# Rs485_current_sense_V1_1.net
KiCad netlist of a schematic drawn in EAGLE
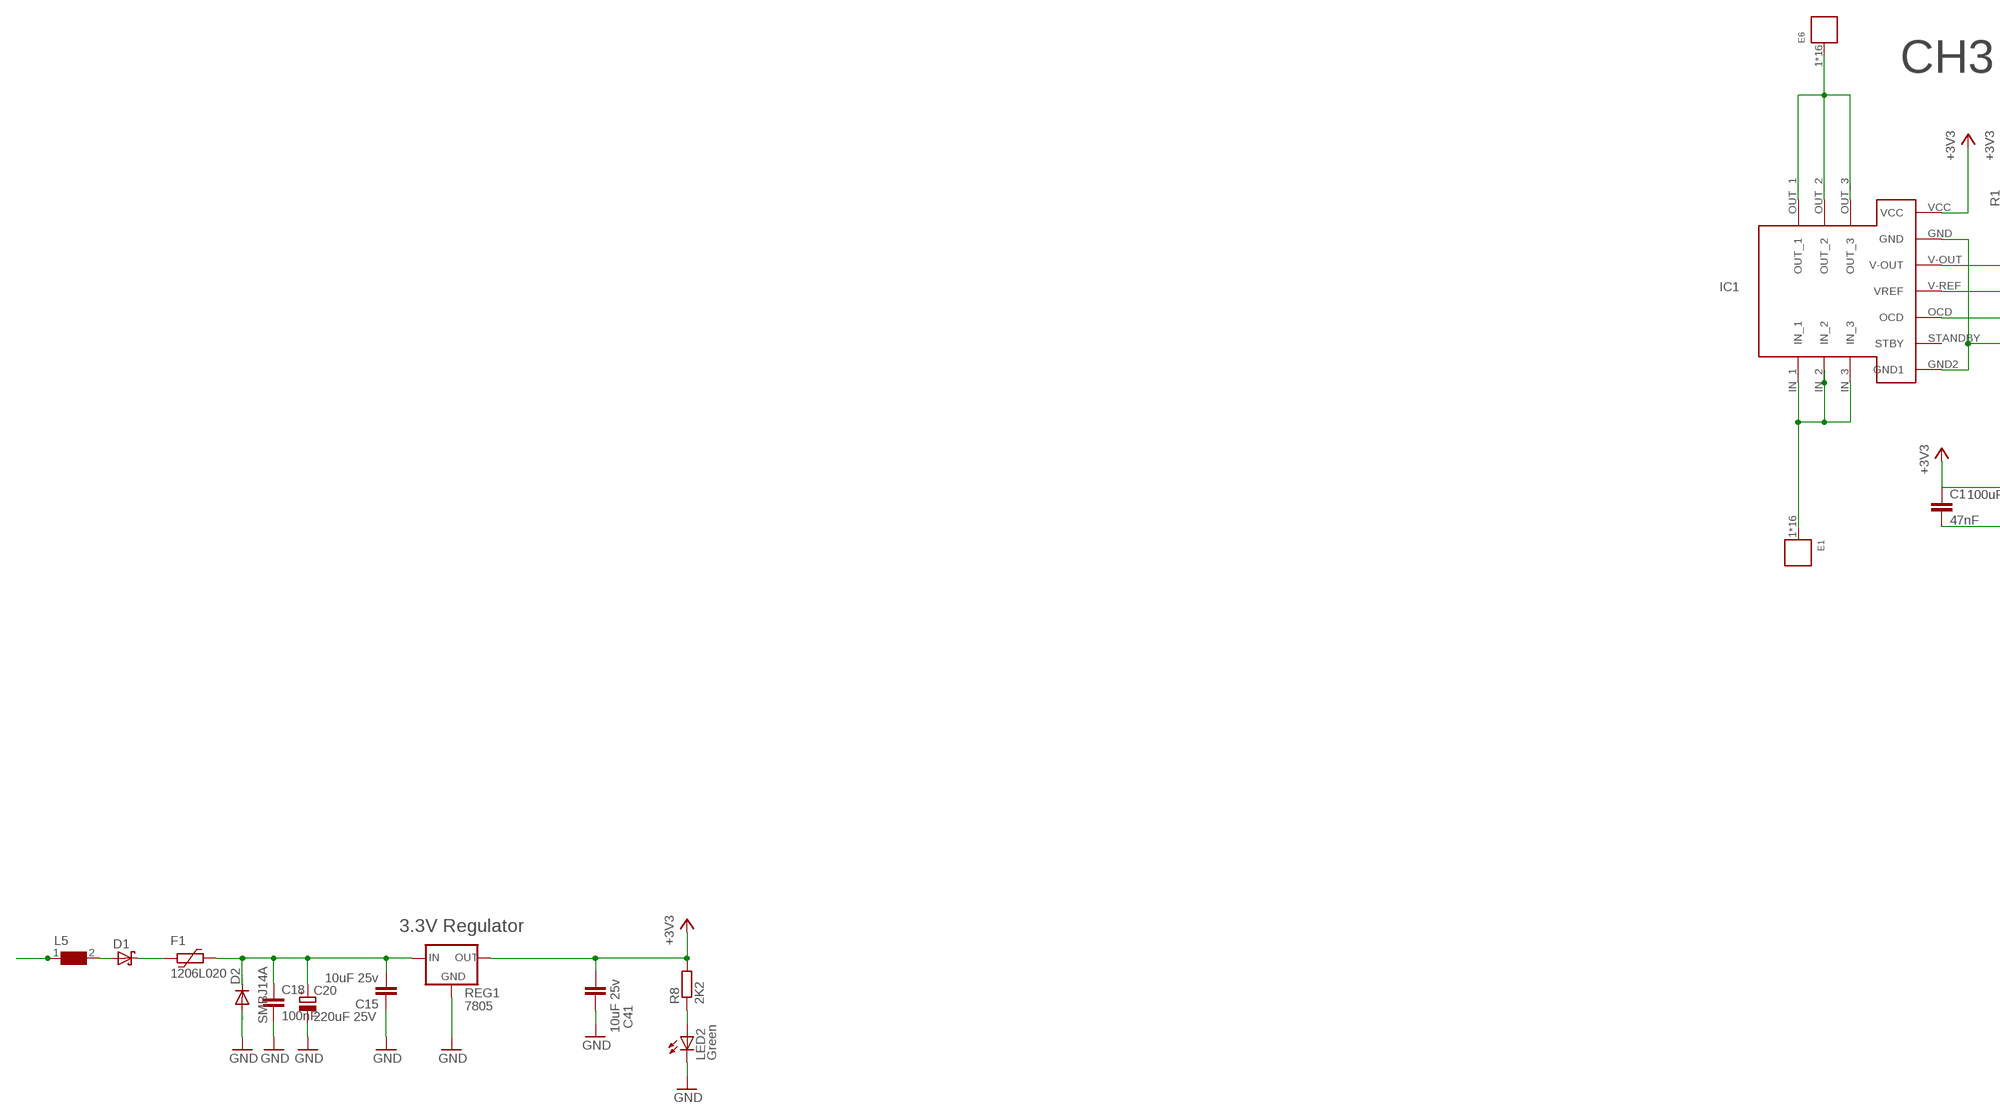
[diagram p0: schematic, sheet 1, part 1 of 3]
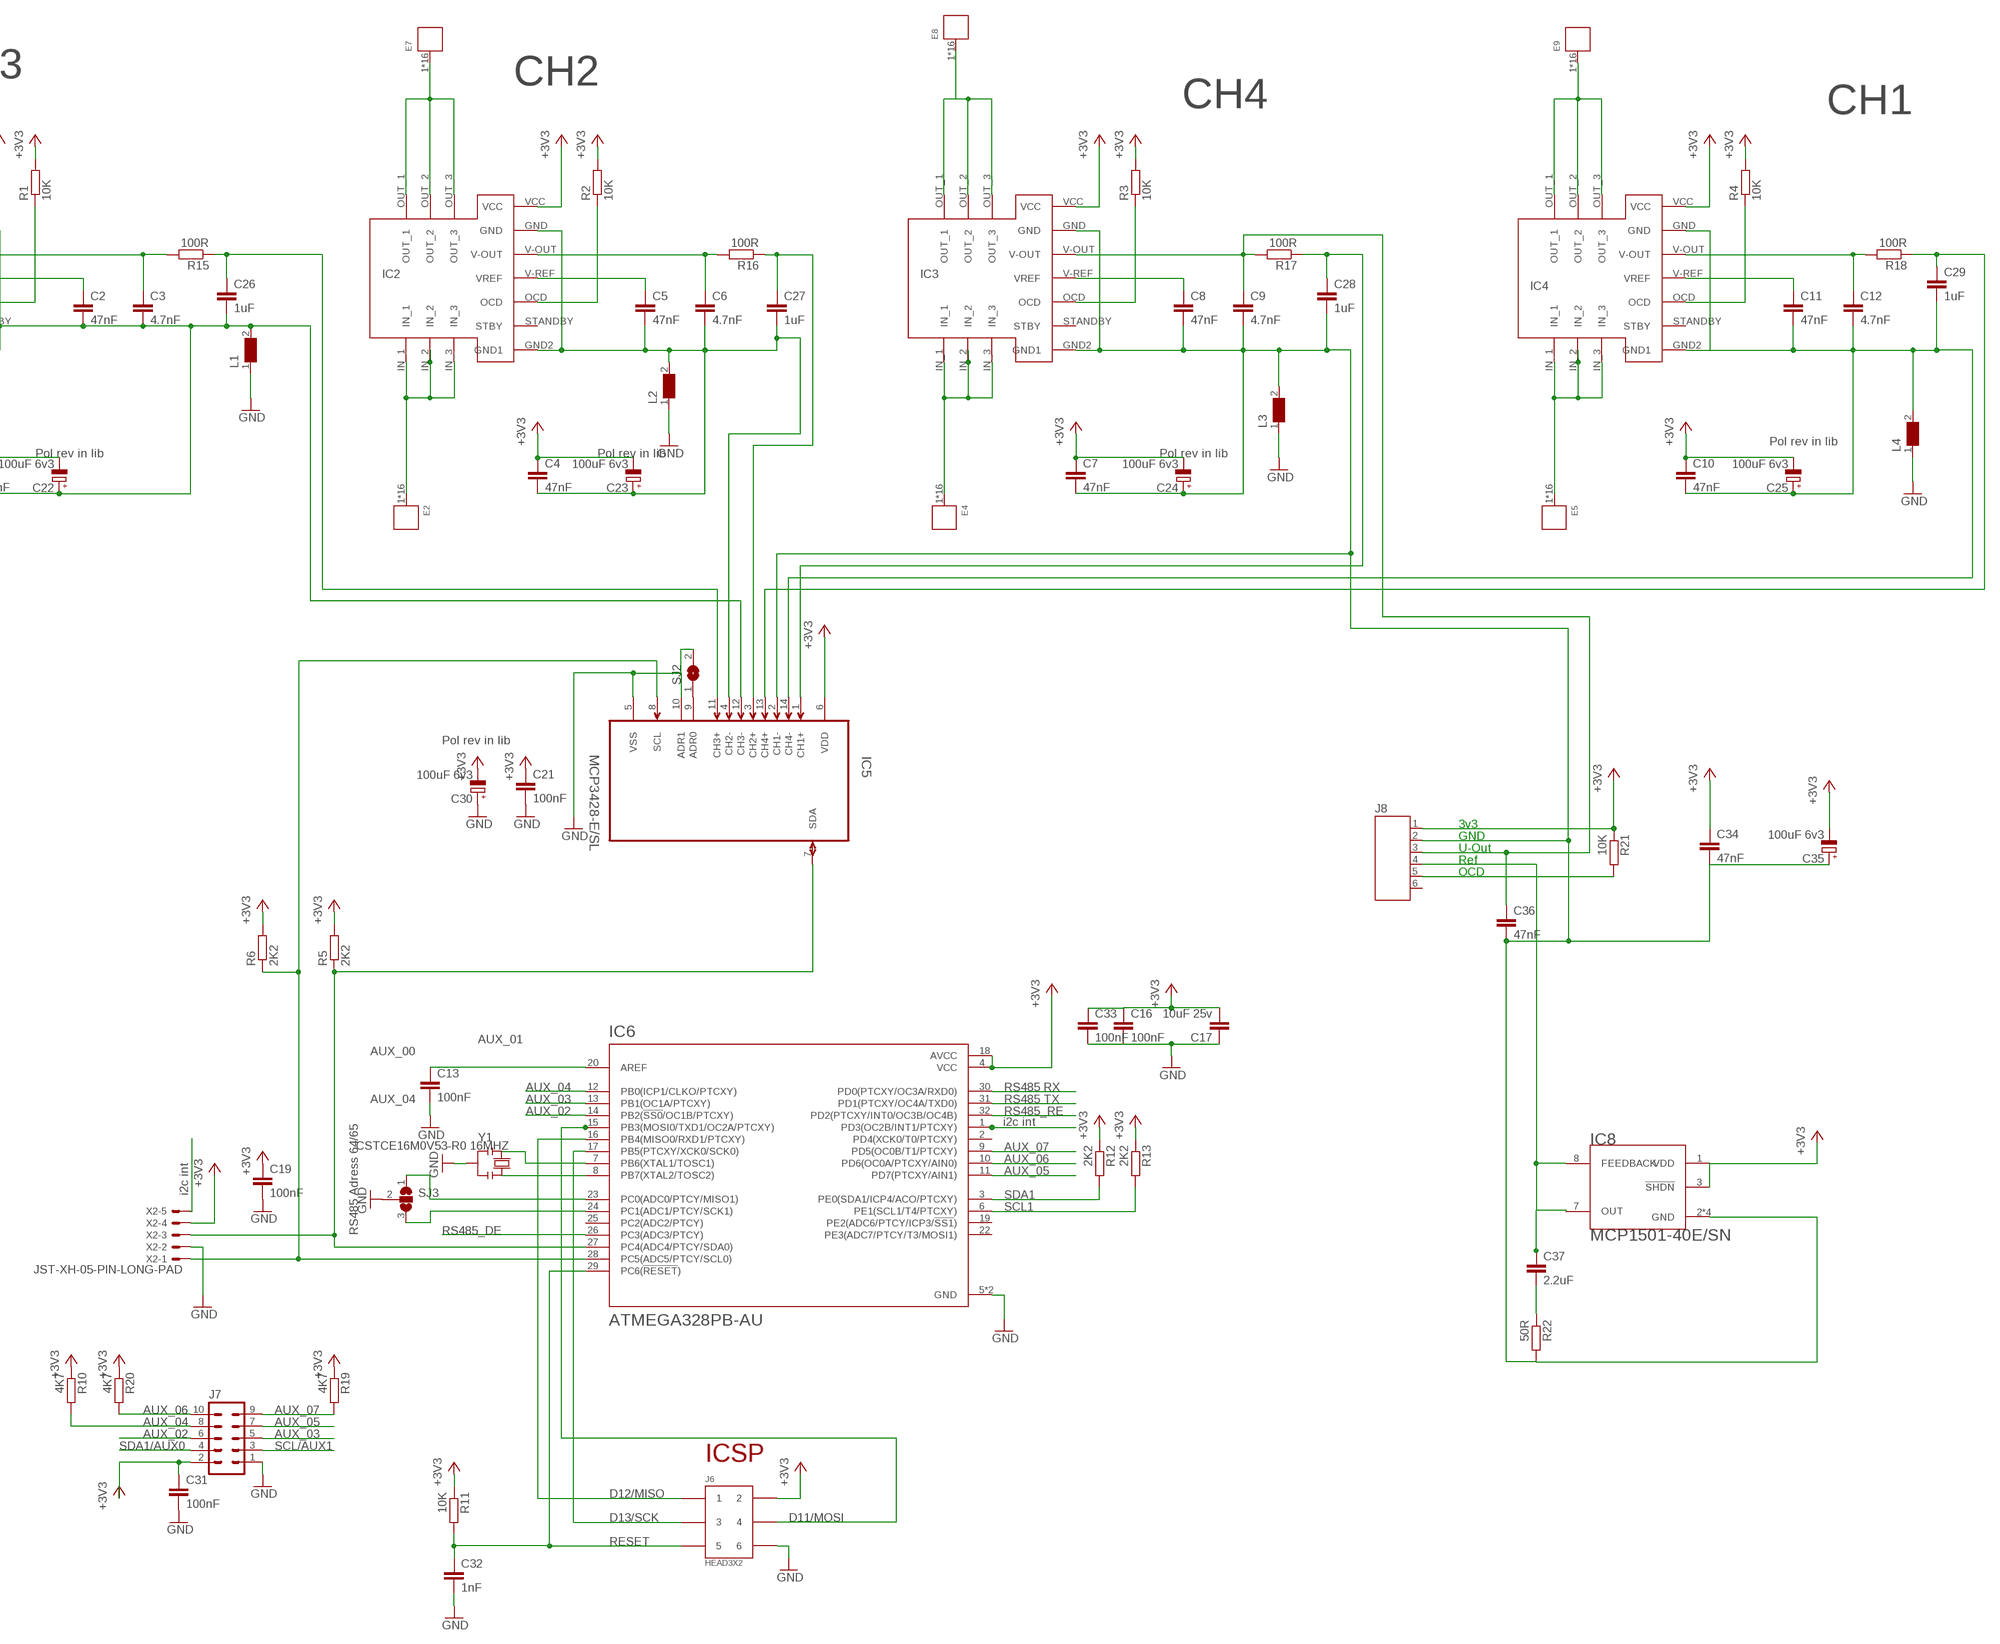
[diagram p1: schematic, sheet 1, part 2 of 3]
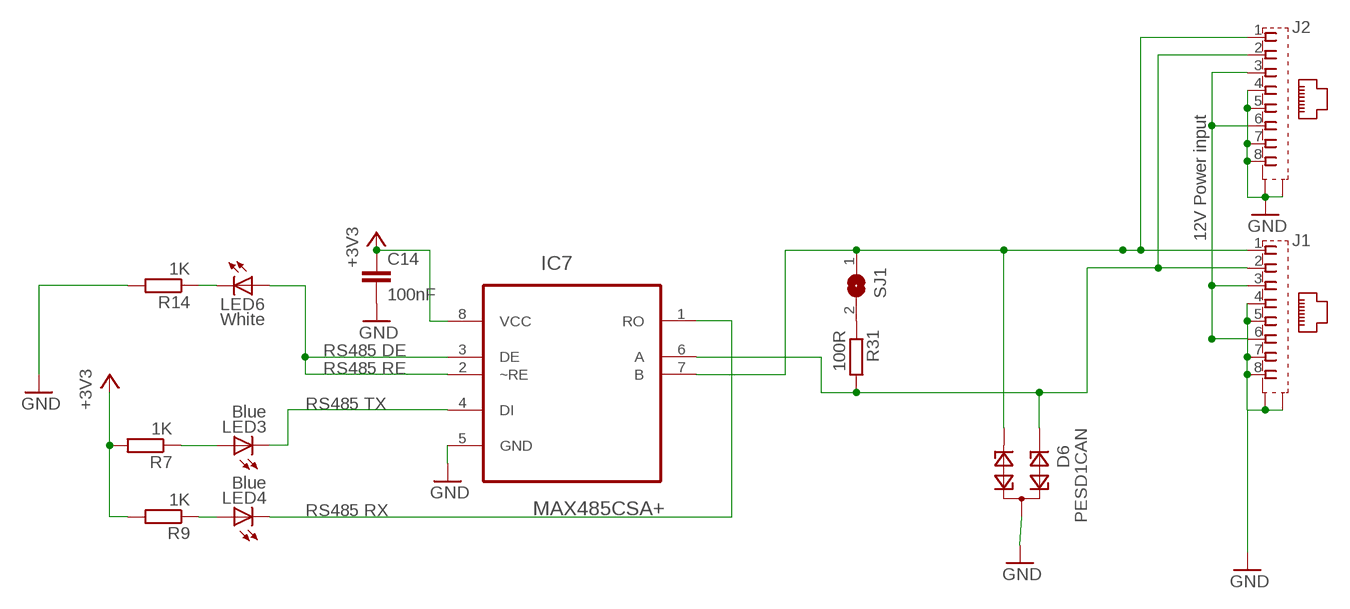
[diagram p2: schematic, sheet 1, part 3 of 3]

(export (version "E")
  (design (tool "Eeschema 10.0.6"))
  (components
    (comp (ref "C1")
      (value "47nF")
      (footprint "eagle-import:C0603")
      (libsource (lib "eagle-import") (part "C-EUC0603"))
    )
    (comp (ref "C2")
      (value "47nF")
      (footprint "eagle-import:C0603")
      (libsource (lib "eagle-import") (part "C-EUC0603"))
    )
    (comp (ref "C3")
      (value "4.7nF")
      (footprint "eagle-import:C0603")
      (libsource (lib "eagle-import") (part "C-EUC0603"))
    )
    (comp (ref "C4")
      (value "47nF")
      (footprint "eagle-import:C0603")
      (libsource (lib "eagle-import") (part "C-EUC0603"))
    )
    (comp (ref "C5")
      (value "47nF")
      (footprint "eagle-import:C0603")
      (libsource (lib "eagle-import") (part "C-EUC0603"))
    )
    (comp (ref "C6")
      (value "4.7nF")
      (footprint "eagle-import:C0603")
      (libsource (lib "eagle-import") (part "C-EUC0603"))
    )
    (comp (ref "C7")
      (value "47nF")
      (footprint "eagle-import:C0603")
      (libsource (lib "eagle-import") (part "C-EUC0603"))
    )
    (comp (ref "C8")
      (value "47nF")
      (footprint "eagle-import:C0603")
      (libsource (lib "eagle-import") (part "C-EUC0603"))
    )
    (comp (ref "C9")
      (value "4.7nF")
      (footprint "eagle-import:C0603")
      (libsource (lib "eagle-import") (part "C-EUC0603"))
    )
    (comp (ref "C10")
      (value "47nF")
      (footprint "eagle-import:C0603")
      (libsource (lib "eagle-import") (part "C-EUC0603"))
    )
    (comp (ref "C11")
      (value "47nF")
      (footprint "eagle-import:C0603")
      (libsource (lib "eagle-import") (part "C-EUC0603"))
    )
    (comp (ref "C12")
      (value "4.7nF")
      (footprint "eagle-import:C0603")
      (libsource (lib "eagle-import") (part "C-EUC0603"))
    )
    (comp (ref "C13")
      (value "100nF")
      (footprint "eagle-import:C0603")
      (libsource (lib "eagle-import") (part "C-EUC0603"))
    )
    (comp (ref "C14")
      (value "100nF")
      (footprint "eagle-import:C0603")
      (libsource (lib "eagle-import") (part "resistor_C-EUC0603"))
    )
    (comp (ref "C15")
      (value "10uF 25v")
      (footprint "eagle-import:C1206")
      (libsource (lib "eagle-import") (part "resistor_C-EUC1206"))
    )
    (comp (ref "C16")
      (value "100nF")
      (footprint "eagle-import:C0603")
      (libsource (lib "eagle-import") (part "C-EUC0603"))
    )
    (comp (ref "C17")
      (value "10uF 25v")
      (footprint "eagle-import:C1206")
      (libsource (lib "eagle-import") (part "resistor_C-EUC1206"))
    )
    (comp (ref "C18")
      (value "100nF")
      (footprint "eagle-import:C0603")
      (libsource (lib "eagle-import") (part "C-EUC0603"))
    )
    (comp (ref "C19")
      (value "100nF")
      (footprint "eagle-import:C0603")
      (libsource (lib "eagle-import") (part "C-EUC0603"))
    )
    (comp (ref "C20")
      (value "220uF 25V")
      (footprint "eagle-import:PANASONIC_F")
      (libsource (lib "eagle-import") (part "CPOL-EUF"))
    )
    (comp (ref "C21")
      (value "100nF")
      (footprint "eagle-import:C0603")
      (libsource (lib "eagle-import") (part "C-EUC0603"))
    )
    (comp (ref "C22")
      (value "100uF 6v3")
      (footprint "eagle-import:CT3528")
      (libsource (lib "eagle-import") (part "resistor_CPOL-EUCT3528"))
    )
    (comp (ref "C23")
      (value "100uF 6v3")
      (footprint "eagle-import:CT3528")
      (libsource (lib "eagle-import") (part "resistor_CPOL-EUCT3528"))
    )
    (comp (ref "C24")
      (value "100uF 6v3")
      (footprint "eagle-import:CT3528")
      (libsource (lib "eagle-import") (part "resistor_CPOL-EUCT3528"))
    )
    (comp (ref "C25")
      (value "100uF 6v3")
      (footprint "eagle-import:CT3528")
      (libsource (lib "eagle-import") (part "resistor_CPOL-EUCT3528"))
    )
    (comp (ref "C26")
      (value "1uF")
      (footprint "eagle-import:C0603")
      (libsource (lib "eagle-import") (part "C-EUC0603"))
    )
    (comp (ref "C27")
      (value "1uF")
      (footprint "eagle-import:C0603")
      (libsource (lib "eagle-import") (part "C-EUC0603"))
    )
    (comp (ref "C28")
      (value "1uF")
      (footprint "eagle-import:C0603")
      (libsource (lib "eagle-import") (part "C-EUC0603"))
    )
    (comp (ref "C29")
      (value "1uF")
      (footprint "eagle-import:C0603")
      (libsource (lib "eagle-import") (part "C-EUC0603"))
    )
    (comp (ref "C30")
      (value "100uF 6v3")
      (footprint "eagle-import:CT3528")
      (libsource (lib "eagle-import") (part "resistor_CPOL-EUCT3528"))
    )
    (comp (ref "C31")
      (value "100nF")
      (footprint "eagle-import:C0603")
      (libsource (lib "eagle-import") (part "C-EUC0603"))
    )
    (comp (ref "C32")
      (value "1nF")
      (footprint "eagle-import:C0603")
      (libsource (lib "eagle-import") (part "C-EUC0603"))
    )
    (comp (ref "C33")
      (value "100nF")
      (footprint "eagle-import:C0603")
      (libsource (lib "eagle-import") (part "C-EUC0603"))
    )
    (comp (ref "C34")
      (value "47nF")
      (footprint "eagle-import:C0603")
      (libsource (lib "eagle-import") (part "C-EUC0603"))
    )
    (comp (ref "C35")
      (value "100uF 6v3")
      (footprint "eagle-import:CT3528")
      (libsource (lib "eagle-import") (part "resistor_CPOL-EUCT3528"))
    )
    (comp (ref "C36")
      (value "47nF")
      (footprint "eagle-import:C0603")
      (libsource (lib "eagle-import") (part "C-EUC0603"))
    )
    (comp (ref "C37")
      (value "2.2uF")
      (footprint "eagle-import:C0805")
      (libsource (lib "eagle-import") (part "resistor_C-EUC0805"))
    )
    (comp (ref "C41")
      (value "10uF 25v")
      (footprint "eagle-import:C1206")
      (libsource (lib "eagle-import") (part "resistor_C-EUC1206"))
    )
    (comp (ref "D1")
      (value "SCHOTTKY-DIODESMD")
      (footprint "eagle-import:SMB")
      (libsource (lib "eagle-import") (part "SCHOTTKY-DIODESMD"))
    )
    (comp (ref "D2")
      (value "SMBJ14A")
      (footprint "eagle-import:DO214AC")
      (libsource (lib "eagle-import") (part "DIODE-DO214AC"))
    )
    (comp (ref "D6")
      (value "PESD1CAN")
      (footprint "eagle-import:SOT23")
      (libsource (lib "eagle-import") (part "PESD1CAN"))
    )
    (comp (ref "E1")
      (value "WP-BUFU_J(10)")
      (footprint "eagle-import:16PINS_10X10_FULL")
      (libsource (lib "eagle-import") (part "WP-BUFU_J(10)"))
    )
    (comp (ref "E2")
      (value "WP-BUFU_J(10)")
      (footprint "eagle-import:16PINS_10X10_FULL")
      (libsource (lib "eagle-import") (part "WP-BUFU_J(10)"))
    )
    (comp (ref "E4")
      (value "WP-BUFU_J(10)")
      (footprint "eagle-import:16PINS_10X10_FULL")
      (libsource (lib "eagle-import") (part "WP-BUFU_J(10)"))
    )
    (comp (ref "E5")
      (value "WP-BUFU_J(10)")
      (footprint "eagle-import:16PINS_10X10_FULL")
      (libsource (lib "eagle-import") (part "WP-BUFU_J(10)"))
    )
    (comp (ref "E6")
      (value "WP-BUFU_J(10)")
      (footprint "eagle-import:16PINS_10X10_FULL")
      (libsource (lib "eagle-import") (part "WP-BUFU_J(10)"))
    )
    (comp (ref "E7")
      (value "WP-BUFU_J(10)")
      (footprint "eagle-import:16PINS_10X10_FULL")
      (libsource (lib "eagle-import") (part "WP-BUFU_J(10)"))
    )
    (comp (ref "E8")
      (value "WP-BUFU_J(10)")
      (footprint "eagle-import:16PINS_10X10_FULL")
      (libsource (lib "eagle-import") (part "WP-BUFU_J(10)"))
    )
    (comp (ref "E9")
      (value "WP-BUFU_J(10)")
      (footprint "eagle-import:16PINS_10X10_FULL")
      (libsource (lib "eagle-import") (part "WP-BUFU_J(10)"))
    )
    (comp (ref "F1")
      (value "1206L020")
      (footprint "eagle-import:1206L")
      (fields (field (name "MF") "Littelfuse"))
      (libsource (lib "eagle-import") (part "?1206L020"))
    )
    (comp (ref "IC1")
      (value "HO15-NP/SP33-1000")
      (footprint "eagle-import:HO15-NP_SP33-1000")
      (libsource (lib "eagle-import") (part "HO15-NP/SP33-1000"))
    )
    (comp (ref "IC2")
      (value "HO15-NP/SP33-1000")
      (footprint "eagle-import:HO15-NP_SP33-1000")
      (libsource (lib "eagle-import") (part "HO15-NP/SP33-1000"))
    )
    (comp (ref "IC3")
      (value "HO15-NP/SP33-1000")
      (footprint "eagle-import:HO15-NP_SP33-1000")
      (libsource (lib "eagle-import") (part "HO15-NP/SP33-1000"))
    )
    (comp (ref "IC4")
      (value "HO15-NP/SP33-1000")
      (footprint "eagle-import:HO15-NP_SP33-1000")
      (libsource (lib "eagle-import") (part "HO15-NP/SP33-1000"))
    )
    (comp (ref "IC5")
      (value "MCP3428-E/SL")
      (footprint "eagle-import:SOIC127P600X175-14N")
      (libsource (lib "eagle-import") (part "MCP3428-E/SL"))
    )
    (comp (ref "IC6")
      (value "ATMEGA328PB-AU")
      (footprint "eagle-import:QFP80P900X900X120-32N")
      (fields (field (name "MF") "Microchip"))
      (libsource (lib "eagle-import") (part "ATMEGA328PB-AU"))
    )
    (comp (ref "IC7")
      (value "MAX485CSA+")
      (footprint "eagle-import:SOIC127P600X175-8N")
      (libsource (lib "eagle-import") (part "MAX485CSA+"))
    )
    (comp (ref "IC8")
      (value "MCP1501-40E/SN")
      (footprint "eagle-import:SOIC127P600X175-8N")
      (fields (field (name "MF") "Microchip"))
      (libsource (lib "eagle-import") (part "MCP1501-40E/SN"))
    )
    (comp (ref "J1")
      (value "555153-1")
      (footprint "eagle-import:555153-1")
      (libsource (lib "eagle-import") (part "555153-1"))
    )
    (comp (ref "J2")
      (value "555153-1")
      (footprint "eagle-import:555153-1")
      (libsource (lib "eagle-import") (part "555153-1"))
    )
    (comp (ref "J6")
      (value "HEAD3X2")
      (footprint "eagle-import:HEAD3X2")
      (libsource (lib "eagle-import") (part "HEAD3X2"))
    )
    (comp (ref "J7")
      (value "MA05-2")
      (footprint "eagle-import:MA05-2")
      (libsource (lib "eagle-import") (part "MA05-2"))
    )
    (comp (ref "J8")
      (value "JST-PH6")
      (footprint "eagle-import:JST-PH6")
      (libsource (lib "eagle-import") (part "JST-PH6"))
    )
    (comp (ref "L1")
      (value "WE-CBF-74279209_0805")
      (footprint "eagle-import:0805")
      (fields (field (name "MPN") "74279209"))
      (libsource (lib "eagle-import") (part "WE-CBF_0805-74279209"))
    )
    (comp (ref "L2")
      (value "WE-CBF-74279209_0805")
      (footprint "eagle-import:0805")
      (fields (field (name "MPN") "74279209"))
      (libsource (lib "eagle-import") (part "WE-CBF_0805-74279209"))
    )
    (comp (ref "L3")
      (value "WE-CBF-74279209_0805")
      (footprint "eagle-import:0805")
      (fields (field (name "MPN") "74279209"))
      (libsource (lib "eagle-import") (part "WE-CBF_0805-74279209"))
    )
    (comp (ref "L4")
      (value "WE-CBF-74279209_0805")
      (footprint "eagle-import:0805")
      (fields (field (name "MPN") "74279209"))
      (libsource (lib "eagle-import") (part "WE-CBF_0805-74279209"))
    )
    (comp (ref "L5")
      (value "WE-CBF-7427922_1206")
      (footprint "eagle-import:1206")
      (fields (field (name "MPN") "7427922"))
      (libsource (lib "eagle-import") (part "WE-CBF_1206-7427922"))
    )
    (comp (ref "LED2")
      (value "Green")
      (footprint "eagle-import:CHIPLED_0805")
      (libsource (lib "eagle-import") (part "LEDCHIPLED_0805"))
    )
    (comp (ref "LED3")
      (value "Blue")
      (footprint "eagle-import:CHIPLED_0805")
      (libsource (lib "eagle-import") (part "LEDCHIPLED_0805"))
    )
    (comp (ref "LED4")
      (value "Blue")
      (footprint "eagle-import:CHIPLED_0805")
      (libsource (lib "eagle-import") (part "LEDCHIPLED_0805"))
    )
    (comp (ref "LED6")
      (value "White")
      (footprint "eagle-import:CHIPLED_0805")
      (libsource (lib "eagle-import") (part "LEDCHIPLED_0805"))
    )
    (comp (ref "R1")
      (value "10K")
      (footprint "eagle-import:R0603")
      (libsource (lib "eagle-import") (part "R-EU_R0603"))
    )
    (comp (ref "R2")
      (value "10K")
      (footprint "eagle-import:R0603")
      (libsource (lib "eagle-import") (part "R-EU_R0603"))
    )
    (comp (ref "R3")
      (value "10K")
      (footprint "eagle-import:R0603")
      (libsource (lib "eagle-import") (part "R-EU_R0603"))
    )
    (comp (ref "R4")
      (value "10K")
      (footprint "eagle-import:R0603")
      (libsource (lib "eagle-import") (part "R-EU_R0603"))
    )
    (comp (ref "R5")
      (value "2K2")
      (footprint "eagle-import:R0603")
      (libsource (lib "eagle-import") (part "R-EU_R0603"))
    )
    (comp (ref "R6")
      (value "2K2")
      (footprint "eagle-import:R0603")
      (libsource (lib "eagle-import") (part "R-EU_R0603"))
    )
    (comp (ref "R7")
      (value "1K")
      (footprint "eagle-import:R0805")
      (libsource (lib "eagle-import") (part "resistor_R-EU_R0805"))
    )
    (comp (ref "R8")
      (value "2K2")
      (footprint "eagle-import:R0805")
      (libsource (lib "eagle-import") (part "resistor_R-EU_R0805"))
    )
    (comp (ref "R9")
      (value "1K")
      (footprint "eagle-import:R0805")
      (libsource (lib "eagle-import") (part "resistor_R-EU_R0805"))
    )
    (comp (ref "R10")
      (value "4K7")
      (footprint "eagle-import:R0603")
      (libsource (lib "eagle-import") (part "resistor_R-EU_R0603"))
    )
    (comp (ref "R11")
      (value "10K")
      (footprint "eagle-import:R0603")
      (libsource (lib "eagle-import") (part "resistor_R-EU_R0603"))
    )
    (comp (ref "R12")
      (value "2K2")
      (footprint "eagle-import:R0603")
      (libsource (lib "eagle-import") (part "resistor_R-EU_R0603"))
    )
    (comp (ref "R13")
      (value "2K2")
      (footprint "eagle-import:R0603")
      (libsource (lib "eagle-import") (part "resistor_R-EU_R0603"))
    )
    (comp (ref "R14")
      (value "1K")
      (footprint "eagle-import:R0805")
      (libsource (lib "eagle-import") (part "resistor_R-EU_R0805"))
    )
    (comp (ref "R15")
      (value "100R")
      (footprint "eagle-import:R0603")
      (libsource (lib "eagle-import") (part "R-EU_R0603"))
    )
    (comp (ref "R16")
      (value "100R")
      (footprint "eagle-import:R0603")
      (libsource (lib "eagle-import") (part "R-EU_R0603"))
    )
    (comp (ref "R17")
      (value "100R")
      (footprint "eagle-import:R0603")
      (libsource (lib "eagle-import") (part "R-EU_R0603"))
    )
    (comp (ref "R18")
      (value "100R")
      (footprint "eagle-import:R0603")
      (libsource (lib "eagle-import") (part "R-EU_R0603"))
    )
    (comp (ref "R19")
      (value "4K7")
      (footprint "eagle-import:R0603")
      (libsource (lib "eagle-import") (part "resistor_R-EU_R0603"))
    )
    (comp (ref "R20")
      (value "4K7")
      (footprint "eagle-import:R0603")
      (libsource (lib "eagle-import") (part "resistor_R-EU_R0603"))
    )
    (comp (ref "R21")
      (value "10K")
      (footprint "eagle-import:R0603")
      (libsource (lib "eagle-import") (part "resistor_R-EU_R0603"))
    )
    (comp (ref "R22")
      (value "50R")
      (footprint "eagle-import:R0603")
      (libsource (lib "eagle-import") (part "resistor_R-EU_R0603"))
    )
    (comp (ref "R31")
      (value "100R")
      (footprint "eagle-import:R0805")
      (libsource (lib "eagle-import") (part "resistor_R-EU_R0805"))
    )
    (comp (ref "REG1")
      (value "7805")
      (footprint "eagle-import:78XXS")
      (libsource (lib "eagle-import") (part "78XXS"))
    )
    (comp (ref "SJ1") (value "SJ") (footprint "eagle-import:SJ") (libsource (lib "eagle-import") (part "SJ")))
    (comp (ref "SJ2") (value "SJ") (footprint "eagle-import:SJ") (libsource (lib "eagle-import") (part "SJ")))
    (comp (ref "SJ3")
      (value "SJ2W")
      (footprint "eagle-import:SJ_2")
      (libsource (lib "eagle-import") (part "SJ2W"))
    )
    (comp (ref "X2")
      (value "JST-XH-05-PIN-LONG-PAD")
      (footprint "eagle-import:JST-XH-05-PACKAGE-LONG-PAD")
      (libsource (lib "eagle-import") (part "JST-XH-05-PIN-LONG-PAD"))
    )
    (comp (ref "Y1")
      (value "CSTCE16M0V53-R0 16MHZ")
      (footprint "eagle-import:RESONATOR")
      (libsource (lib "eagle-import") (part "RESONATORMU"))
    )
  )
  (nets
    (net (code "1") (name "+3V3") (class "Default")
      (node (ref "C1") (pin "1") (pinfunction "1_1") (pintype "passive"))
      (node (ref "C10") (pin "1") (pinfunction "1_1") (pintype "passive"))
      (node (ref "C14") (pin "1") (pinfunction "1_1") (pintype "passive"))
      (node (ref "C16") (pin "1") (pinfunction "1_1") (pintype "passive"))
      (node (ref "C17") (pin "2") (pinfunction "2_2") (pintype "passive"))
      (node (ref "C19") (pin "1") (pinfunction "1_1") (pintype "passive"))
      (node (ref "C21") (pin "1") (pinfunction "1_1") (pintype "passive"))
      (node (ref "C22") (pin "+") (pinfunction "-_+") (pintype "passive"))
      (node (ref "C23") (pin "+") (pinfunction "-_+") (pintype "passive"))
      (node (ref "C24") (pin "+") (pinfunction "-_+") (pintype "passive"))
      (node (ref "C25") (pin "+") (pinfunction "-_+") (pintype "passive"))
      (node (ref "C30") (pin "+") (pinfunction "-_+") (pintype "passive"))
      (node (ref "C31") (pin "1") (pinfunction "1_1") (pintype "passive"))
      (node (ref "C33") (pin "1") (pinfunction "1_1") (pintype "passive"))
      (node (ref "C34") (pin "1") (pinfunction "1_1") (pintype "passive"))
      (node (ref "C35") (pin "+") (pinfunction "-_+") (pintype "passive"))
      (node (ref "C4") (pin "1") (pinfunction "1_1") (pintype "passive"))
      (node (ref "C41") (pin "2") (pinfunction "2_2") (pintype "passive"))
      (node (ref "C7") (pin "1") (pinfunction "1_1") (pintype "passive"))
      (node (ref "IC1") (pin "VCC") (pinfunction "VCC_VCC") (pintype "bidirectional"))
      (node (ref "IC2") (pin "VCC") (pinfunction "VCC_VCC") (pintype "bidirectional"))
      (node (ref "IC3") (pin "VCC") (pinfunction "VCC_VCC") (pintype "bidirectional"))
      (node (ref "IC4") (pin "VCC") (pinfunction "VCC_VCC") (pintype "bidirectional"))
      (node (ref "IC5") (pin "6") (pinfunction "VDD_6") (pintype "power_in"))
      (node (ref "IC6") (pin "18") (pinfunction "AVCC_18") (pintype "power_in"))
      (node (ref "IC6") (pin "4") (pinfunction "VCC_4") (pintype "power_in"))
      (node (ref "IC7") (pin "8") (pinfunction "VCC_8") (pintype "power_in"))
      (node (ref "IC8") (pin "1") (pinfunction "VDD_1") (pintype "power_in"))
      (node (ref "IC8") (pin "3") (pinfunction "~{SHDN}_3") (pintype "input"))
      (node (ref "J6") (pin "2") (pinfunction "2_2") (pintype "passive"))
      (node (ref "J7") (pin "2") (pinfunction "2_2") (pintype "passive"))
      (node (ref "J8") (pin "1") (pinfunction "1_1") (pintype "passive"))
      (node (ref "R1") (pin "2") (pinfunction "2_2") (pintype "passive"))
      (node (ref "R10") (pin "1") (pinfunction "1_1") (pintype "passive"))
      (node (ref "R11") (pin "1") (pinfunction "1_1") (pintype "passive"))
      (node (ref "R12") (pin "1") (pinfunction "1_1") (pintype "passive"))
      (node (ref "R13") (pin "1") (pinfunction "1_1") (pintype "passive"))
      (node (ref "R19") (pin "1") (pinfunction "1_1") (pintype "passive"))
      (node (ref "R2") (pin "2") (pinfunction "2_2") (pintype "passive"))
      (node (ref "R20") (pin "1") (pinfunction "1_1") (pintype "passive"))
      (node (ref "R21") (pin "1") (pinfunction "1_1") (pintype "passive"))
      (node (ref "R3") (pin "2") (pinfunction "2_2") (pintype "passive"))
      (node (ref "R4") (pin "2") (pinfunction "2_2") (pintype "passive"))
      (node (ref "R5") (pin "2") (pinfunction "2_2") (pintype "passive"))
      (node (ref "R6") (pin "2") (pinfunction "2_2") (pintype "passive"))
      (node (ref "R7") (pin "2") (pinfunction "2_2") (pintype "passive"))
      (node (ref "R8") (pin "2") (pinfunction "2_2") (pintype "passive"))
      (node (ref "R9") (pin "2") (pinfunction "2_2") (pintype "passive"))
      (node (ref "REG1") (pin "OUT") (pinfunction "OUT_OUT") (pintype "passive"))
      (node (ref "X2") (pin "4") (pinfunction "S_4") (pintype "passive"))
    )
    (net (code "2") (name "/12V") (class "Default")
      (node (ref "J1") (pin "3") (pinfunction "3_3") (pintype "passive"))
      (node (ref "J1") (pin "6") (pinfunction "6_6") (pintype "passive"))
      (node (ref "J2") (pin "3") (pinfunction "3_3") (pintype "passive"))
      (node (ref "J2") (pin "6") (pinfunction "6_6") (pintype "passive"))
      (node (ref "L5") (pin "1") (pinfunction "1_1") (pintype "passive"))
    )
    (net (code "3") (name "/AUX_02") (class "Default")
      (node (ref "IC6") (pin "14") (pinfunction "PB2(~{SS0}/OC1B/PTCXY)_14") (pintype "bidirectional"))
      (node (ref "J7") (pin "6") (pinfunction "6_6") (pintype "passive"))
    )
    (net (code "4") (name "/AUX_03") (class "Default")
      (node (ref "IC6") (pin "13") (pinfunction "PB1(OC1A/PTCXY)_13") (pintype "bidirectional"))
      (node (ref "J7") (pin "5") (pinfunction "5_5") (pintype "passive"))
    )
    (net (code "5") (name "/AUX_04") (class "Default")
      (node (ref "IC6") (pin "12") (pinfunction "PB0(ICP1/CLKO/PTCXY)_12") (pintype "bidirectional"))
      (node (ref "J7") (pin "8") (pinfunction "8_8") (pintype "passive"))
      (node (ref "R10") (pin "2") (pinfunction "2_2") (pintype "passive"))
    )
    (net (code "6") (name "/AUX_05") (class "Default")
      (node (ref "IC6") (pin "11") (pinfunction "PD7(PTCXY/AIN1)_11") (pintype "bidirectional"))
      (node (ref "J7") (pin "7") (pinfunction "7_7") (pintype "passive"))
    )
    (net (code "7") (name "/AUX_06") (class "Default")
      (node (ref "IC6") (pin "10") (pinfunction "PD6(OC0A/PTCXY/AIN0)_10") (pintype "bidirectional"))
      (node (ref "J7") (pin "10") (pinfunction "10_10") (pintype "passive"))
      (node (ref "R20") (pin "2") (pinfunction "2_2") (pintype "passive"))
    )
    (net (code "8") (name "/AUX_07") (class "Default")
      (node (ref "IC6") (pin "9") (pinfunction "PD5(OC0B/T1/PTCXY)_9") (pintype "bidirectional"))
      (node (ref "J7") (pin "9") (pinfunction "9_9") (pintype "passive"))
      (node (ref "R19") (pin "2") (pinfunction "2_2") (pintype "passive"))
    )
    (net (code "9") (name "/D11{slash}MOSI") (class "Default")
      (node (ref "IC6") (pin "15") (pinfunction "PB3(MOSI0/TXD1/OC2A/PTCXY)_15") (pintype "bidirectional"))
      (node (ref "J6") (pin "4") (pinfunction "4_4") (pintype "passive"))
    )
    (net (code "10") (name "/D12{slash}MISO") (class "Default")
      (node (ref "IC6") (pin "16") (pinfunction "PB4(MISO0/RXD1/PTCXY)_16") (pintype "bidirectional"))
      (node (ref "J6") (pin "1") (pinfunction "1_1") (pintype "passive"))
    )
    (net (code "11") (name "/D13{slash}SCK") (class "Default")
      (node (ref "IC6") (pin "17") (pinfunction "PB5(PTCXY/XCK0/SCK0)_17") (pintype "bidirectional"))
      (node (ref "J6") (pin "3") (pinfunction "3_3") (pintype "passive"))
    )
    (net (code "12") (name "/I2C_INT") (class "Default")
      (node (ref "IC6") (pin "1") (pinfunction "PD3(OC2B/INT1/PTCXY)_1") (pintype "bidirectional"))
      (node (ref "X2") (pin "5") (pinfunction "S_5") (pintype "passive"))
    )
    (net (code "13") (name "/RESET") (class "Default")
      (node (ref "C32") (pin "1") (pinfunction "1_1") (pintype "passive"))
      (node (ref "IC6") (pin "29") (pinfunction "PC6(~{RESET})_29") (pintype "bidirectional"))
      (node (ref "J6") (pin "5") (pinfunction "5_5") (pintype "passive"))
      (node (ref "R11") (pin "2") (pinfunction "2_2") (pintype "passive"))
    )
    (net (code "14") (name "/RS485_DE") (class "Default")
      (node (ref "IC6") (pin "26") (pinfunction "PC3(ADC3/PTCY)_26") (pintype "bidirectional"))
      (node (ref "IC7") (pin "2") (pinfunction "~{RE}_2") (pintype "input"))
      (node (ref "IC7") (pin "3") (pinfunction "DE_3") (pintype "input"))
      (node (ref "LED6") (pin "A") (pinfunction "A_A") (pintype "passive"))
    )
    (net (code "15") (name "/RS485_RX") (class "Default")
      (node (ref "IC6") (pin "30") (pinfunction "PD0(PTCXY/OC3A/RXD0)_30") (pintype "bidirectional"))
      (node (ref "IC7") (pin "1") (pinfunction "RO_1") (pintype "output"))
      (node (ref "LED4") (pin "C") (pinfunction "C_C") (pintype "passive"))
    )
    (net (code "16") (name "/RS485_TX") (class "Default")
      (node (ref "IC6") (pin "31") (pinfunction "PD1(PTCXY/OC4A/TXD0)_31") (pintype "bidirectional"))
      (node (ref "IC7") (pin "4") (pinfunction "DI_4") (pintype "input"))
      (node (ref "LED3") (pin "C") (pinfunction "C_C") (pintype "passive"))
    )
    (net (code "17") (name "/SCL1") (class "Default")
      (node (ref "IC6") (pin "6") (pinfunction "PE1(SCL1/T4/PTCXY)_6") (pintype "bidirectional"))
      (node (ref "J7") (pin "3") (pinfunction "3_3") (pintype "passive"))
      (node (ref "R13") (pin "2") (pinfunction "2_2") (pintype "passive"))
    )
    (net (code "18") (name "/SDA1") (class "Default")
      (node (ref "IC6") (pin "3") (pinfunction "PE0(SDA1/ICP4/ACO/PTCXY)_3") (pintype "bidirectional"))
      (node (ref "J7") (pin "4") (pinfunction "4_4") (pintype "passive"))
      (node (ref "R12") (pin "2") (pinfunction "2_2") (pintype "passive"))
    )
    (net (code "19") (name "GND") (class "Default")
      (node (ref "C13") (pin "2") (pinfunction "2_2") (pintype "passive"))
      (node (ref "C14") (pin "2") (pinfunction "2_2") (pintype "passive"))
      (node (ref "C15") (pin "1") (pinfunction "1_1") (pintype "passive"))
      (node (ref "C16") (pin "2") (pinfunction "2_2") (pintype "passive"))
      (node (ref "C17") (pin "1") (pinfunction "1_1") (pintype "passive"))
      (node (ref "C18") (pin "2") (pinfunction "2_2") (pintype "passive"))
      (node (ref "C19") (pin "2") (pinfunction "2_2") (pintype "passive"))
      (node (ref "C20") (pin "-") (pinfunction "-_-") (pintype "passive"))
      (node (ref "C21") (pin "2") (pinfunction "2_2") (pintype "passive"))
      (node (ref "C30") (pin "-") (pinfunction "+_-") (pintype "passive"))
      (node (ref "C31") (pin "2") (pinfunction "2_2") (pintype "passive"))
      (node (ref "C32") (pin "2") (pinfunction "2_2") (pintype "passive"))
      (node (ref "C33") (pin "2") (pinfunction "2_2") (pintype "passive"))
      (node (ref "C41") (pin "1") (pinfunction "1_1") (pintype "passive"))
      (node (ref "D2") (pin "A") (pinfunction "A_A") (pintype "passive"))
      (node (ref "D6") (pin "3") (pinfunction "3_3") (pintype "passive"))
      (node (ref "IC5") (pin "10") (pinfunction "ADR1_10") (pintype "passive"))
      (node (ref "IC5") (pin "5") (pinfunction "VSS_5") (pintype "power_in"))
      (node (ref "IC6") (pin "21") (pinfunction "GND_21") (pintype "power_in"))
      (node (ref "IC6") (pin "5") (pinfunction "GND_5") (pintype "power_in"))
      (node (ref "IC7") (pin "5") (pinfunction "GND_5") (pintype "passive"))
      (node (ref "J1") (pin "4") (pinfunction "4_4") (pintype "passive"))
      (node (ref "J1") (pin "5") (pinfunction "5_5") (pintype "passive"))
      (node (ref "J1") (pin "7") (pinfunction "7_7") (pintype "passive"))
      (node (ref "J1") (pin "8") (pinfunction "8_8") (pintype "passive"))
      (node (ref "J1") (pin "G1") (pinfunction "S1_G1") (pintype "passive"))
      (node (ref "J1") (pin "G2") (pinfunction "S2_G2") (pintype "passive"))
      (node (ref "J2") (pin "4") (pinfunction "4_4") (pintype "passive"))
      (node (ref "J2") (pin "5") (pinfunction "5_5") (pintype "passive"))
      (node (ref "J2") (pin "7") (pinfunction "7_7") (pintype "passive"))
      (node (ref "J2") (pin "8") (pinfunction "8_8") (pintype "passive"))
      (node (ref "J2") (pin "G1") (pinfunction "S1_G1") (pintype "passive"))
      (node (ref "J2") (pin "G2") (pinfunction "S2_G2") (pintype "passive"))
      (node (ref "J6") (pin "6") (pinfunction "6_6") (pintype "passive"))
      (node (ref "J7") (pin "1") (pinfunction "1_1") (pintype "passive"))
      (node (ref "L1") (pin "1") (pinfunction "1_1") (pintype "passive"))
      (node (ref "L2") (pin "1") (pinfunction "1_1") (pintype "passive"))
      (node (ref "L3") (pin "1") (pinfunction "1_1") (pintype "passive"))
      (node (ref "L4") (pin "1") (pinfunction "1_1") (pintype "passive"))
      (node (ref "LED2") (pin "C") (pinfunction "C_C") (pintype "passive"))
      (node (ref "R14") (pin "2") (pinfunction "2_2") (pintype "passive"))
      (node (ref "REG1") (pin "GND") (pinfunction "GND_GND") (pintype "input"))
      (node (ref "SJ2") (pin "2") (pinfunction "2_2") (pintype "passive"))
      (node (ref "SJ3") (pin "2") (pinfunction "2_2") (pintype "passive"))
      (node (ref "X2") (pin "2") (pinfunction "S_2") (pintype "passive"))
      (node (ref "Y1") (pin "2") (pinfunction "2_2") (pintype "passive"))
    )
    (net (code "20") (name "Net-(C3-Pad1)") (class "Default")
      (node (ref "C3") (pin "1") (pinfunction "1_1") (pintype "passive"))
      (node (ref "IC1") (pin "V-OUT") (pinfunction "V-OUT_V-OUT") (pintype "bidirectional"))
      (node (ref "R15") (pin "2") (pinfunction "2_2") (pintype "passive"))
    )
    (net (code "21") (name "Net-(C6-Pad1)") (class "Default")
      (node (ref "C6") (pin "1") (pinfunction "1_1") (pintype "passive"))
      (node (ref "IC2") (pin "V-OUT") (pinfunction "V-OUT_V-OUT") (pintype "bidirectional"))
      (node (ref "R16") (pin "2") (pinfunction "2_2") (pintype "passive"))
    )
    (net (code "22") (name "Net-(C12-Pad1)") (class "Default")
      (node (ref "C12") (pin "1") (pinfunction "1_1") (pintype "passive"))
      (node (ref "IC4") (pin "V-OUT") (pinfunction "V-OUT_V-OUT") (pintype "bidirectional"))
      (node (ref "R18") (pin "2") (pinfunction "2_2") (pintype "passive"))
    )
    (net (code "23") (name "Net-(C15-Pad2)") (class "Default")
      (node (ref "C15") (pin "2") (pinfunction "2_2") (pintype "passive"))
      (node (ref "C18") (pin "1") (pinfunction "1_1") (pintype "passive"))
      (node (ref "C20") (pin "+") (pinfunction "+_+") (pintype "passive"))
      (node (ref "D2") (pin "C") (pinfunction "C_C") (pintype "passive"))
      (node (ref "F1") (pin "1") (pinfunction "1_1") (pintype "passive"))
      (node (ref "REG1") (pin "IN") (pinfunction "IN_IN") (pintype "input"))
    )
    (net (code "24") (name "Net-(C22-+)") (class "Default")
      (node (ref "C1") (pin "2") (pinfunction "2_2") (pintype "passive"))
      (node (ref "C2") (pin "2") (pinfunction "2_2") (pintype "passive"))
      (node (ref "C22") (pin "-") (pinfunction "+_-") (pintype "passive"))
      (node (ref "C26") (pin "2") (pinfunction "2_2") (pintype "passive"))
      (node (ref "C3") (pin "2") (pinfunction "2_2") (pintype "passive"))
      (node (ref "IC1") (pin "GND") (pinfunction "GND_GND") (pintype "bidirectional"))
      (node (ref "IC1") (pin "GND2") (pinfunction "GND1_GND2") (pintype "bidirectional"))
      (node (ref "IC5") (pin "12") (pinfunction "CH3-_12") (pintype "input"))
      (node (ref "L1") (pin "2") (pinfunction "2_2") (pintype "passive"))
    )
    (net (code "25") (name "Net-(C23-+)") (class "Default")
      (node (ref "C23") (pin "-") (pinfunction "+_-") (pintype "passive"))
      (node (ref "C27") (pin "2") (pinfunction "2_2") (pintype "passive"))
      (node (ref "C4") (pin "2") (pinfunction "2_2") (pintype "passive"))
      (node (ref "C5") (pin "2") (pinfunction "2_2") (pintype "passive"))
      (node (ref "C6") (pin "2") (pinfunction "2_2") (pintype "passive"))
      (node (ref "IC2") (pin "GND") (pinfunction "GND_GND") (pintype "bidirectional"))
      (node (ref "IC2") (pin "GND2") (pinfunction "GND1_GND2") (pintype "bidirectional"))
      (node (ref "IC5") (pin "4") (pinfunction "CH2-_4") (pintype "input"))
      (node (ref "L2") (pin "2") (pinfunction "2_2") (pintype "passive"))
    )
    (net (code "26") (name "Net-(C24-+)") (class "Default")
      (node (ref "C24") (pin "-") (pinfunction "+_-") (pintype "passive"))
      (node (ref "C28") (pin "2") (pinfunction "2_2") (pintype "passive"))
      (node (ref "C34") (pin "2") (pinfunction "2_2") (pintype "passive"))
      (node (ref "C35") (pin "-") (pinfunction "+_-") (pintype "passive"))
      (node (ref "C36") (pin "2") (pinfunction "2_2") (pintype "passive"))
      (node (ref "C7") (pin "2") (pinfunction "2_2") (pintype "passive"))
      (node (ref "C8") (pin "2") (pinfunction "2_2") (pintype "passive"))
      (node (ref "C9") (pin "2") (pinfunction "2_2") (pintype "passive"))
      (node (ref "IC3") (pin "GND") (pinfunction "GND_GND") (pintype "bidirectional"))
      (node (ref "IC3") (pin "GND2") (pinfunction "GND1_GND2") (pintype "bidirectional"))
      (node (ref "IC5") (pin "2") (pinfunction "CH1-_2") (pintype "input"))
      (node (ref "IC8") (pin "2") (pinfunction "GND_2") (pintype "passive"))
      (node (ref "IC8") (pin "4") (pinfunction "GND_4") (pintype "passive"))
      (node (ref "IC8") (pin "5") (pinfunction "GND_5") (pintype "passive"))
      (node (ref "IC8") (pin "6") (pinfunction "GND_6") (pintype "passive"))
      (node (ref "J8") (pin "2") (pinfunction "2_2") (pintype "passive"))
      (node (ref "L3") (pin "2") (pinfunction "2_2") (pintype "passive"))
      (node (ref "R22") (pin "2") (pinfunction "2_2") (pintype "passive"))
    )
    (net (code "27") (name "Net-(C25-+)") (class "Default")
      (node (ref "C10") (pin "2") (pinfunction "2_2") (pintype "passive"))
      (node (ref "C11") (pin "2") (pinfunction "2_2") (pintype "passive"))
      (node (ref "C12") (pin "2") (pinfunction "2_2") (pintype "passive"))
      (node (ref "C25") (pin "-") (pinfunction "+_-") (pintype "passive"))
      (node (ref "C29") (pin "2") (pinfunction "2_2") (pintype "passive"))
      (node (ref "IC4") (pin "GND") (pinfunction "GND_GND") (pintype "bidirectional"))
      (node (ref "IC4") (pin "GND2") (pinfunction "GND1_GND2") (pintype "bidirectional"))
      (node (ref "IC5") (pin "14") (pinfunction "CH4-_14") (pintype "input"))
      (node (ref "L4") (pin "2") (pinfunction "2_2") (pintype "passive"))
    )
    (net (code "28") (name "Net-(C36-Pad1)") (class "Default")
      (node (ref "C36") (pin "1") (pinfunction "1_1") (pintype "passive"))
      (node (ref "C9") (pin "1") (pinfunction "1_1") (pintype "passive"))
      (node (ref "IC3") (pin "V-OUT") (pinfunction "V-OUT_V-OUT") (pintype "bidirectional"))
      (node (ref "J8") (pin "3") (pinfunction "3_3") (pintype "passive"))
      (node (ref "R17") (pin "2") (pinfunction "2_2") (pintype "passive"))
    )
    (net (code "29") (name "Net-(C37-Pad2)") (class "Default")
      (node (ref "C37") (pin "2") (pinfunction "2_2") (pintype "passive"))
      (node (ref "R22") (pin "1") (pinfunction "1_1") (pintype "passive"))
    )
    (net (code "30") (name "Net-(D1-PadA)") (class "Default")
      (node (ref "D1") (pin "A") (pinfunction "A_A") (pintype "passive"))
      (node (ref "L5") (pin "2") (pinfunction "2_2") (pintype "passive"))
    )
    (net (code "31") (name "Net-(D1-PadC)") (class "Default")
      (node (ref "D1") (pin "C") (pinfunction "C_C") (pintype "passive"))
      (node (ref "F1") (pin "2") (pinfunction "2_2") (pintype "passive"))
    )
    (net (code "32") (name "Net-(E1-1-Pad10)") (class "Default")
      (node (ref "E1") (pin "1") (pinfunction "1_1") (pintype "passive"))
      (node (ref "E1") (pin "10") (pinfunction "1_10") (pintype "passive"))
      (node (ref "E1") (pin "11") (pinfunction "1_11") (pintype "passive"))
      (node (ref "E1") (pin "12") (pinfunction "1_12") (pintype "passive"))
      (node (ref "E1") (pin "13") (pinfunction "1_13") (pintype "passive"))
      (node (ref "E1") (pin "14") (pinfunction "1_14") (pintype "passive"))
      (node (ref "E1") (pin "15") (pinfunction "1_15") (pintype "passive"))
      (node (ref "E1") (pin "16") (pinfunction "1_16") (pintype "passive"))
      (node (ref "E1") (pin "2") (pinfunction "1_2") (pintype "passive"))
      (node (ref "E1") (pin "3") (pinfunction "1_3") (pintype "passive"))
      (node (ref "E1") (pin "4") (pinfunction "1_4") (pintype "passive"))
      (node (ref "E1") (pin "5") (pinfunction "1_5") (pintype "passive"))
      (node (ref "E1") (pin "6") (pinfunction "1_6") (pintype "passive"))
      (node (ref "E1") (pin "7") (pinfunction "1_7") (pintype "passive"))
      (node (ref "E1") (pin "8") (pinfunction "1_8") (pintype "passive"))
      (node (ref "E1") (pin "9") (pinfunction "1_9") (pintype "passive"))
      (node (ref "IC1") (pin "IN_1") (pinfunction "IN_1_IN_1") (pintype "bidirectional"))
      (node (ref "IC1") (pin "IN_2") (pinfunction "IN_2_IN_2") (pintype "bidirectional"))
      (node (ref "IC1") (pin "IN_3") (pinfunction "IN_3_IN_3") (pintype "bidirectional"))
    )
    (net (code "33") (name "Net-(E2-1-Pad10)") (class "Default")
      (node (ref "E2") (pin "1") (pinfunction "1_1") (pintype "passive"))
      (node (ref "E2") (pin "10") (pinfunction "1_10") (pintype "passive"))
      (node (ref "E2") (pin "11") (pinfunction "1_11") (pintype "passive"))
      (node (ref "E2") (pin "12") (pinfunction "1_12") (pintype "passive"))
      (node (ref "E2") (pin "13") (pinfunction "1_13") (pintype "passive"))
      (node (ref "E2") (pin "14") (pinfunction "1_14") (pintype "passive"))
      (node (ref "E2") (pin "15") (pinfunction "1_15") (pintype "passive"))
      (node (ref "E2") (pin "16") (pinfunction "1_16") (pintype "passive"))
      (node (ref "E2") (pin "2") (pinfunction "1_2") (pintype "passive"))
      (node (ref "E2") (pin "3") (pinfunction "1_3") (pintype "passive"))
      (node (ref "E2") (pin "4") (pinfunction "1_4") (pintype "passive"))
      (node (ref "E2") (pin "5") (pinfunction "1_5") (pintype "passive"))
      (node (ref "E2") (pin "6") (pinfunction "1_6") (pintype "passive"))
      (node (ref "E2") (pin "7") (pinfunction "1_7") (pintype "passive"))
      (node (ref "E2") (pin "8") (pinfunction "1_8") (pintype "passive"))
      (node (ref "E2") (pin "9") (pinfunction "1_9") (pintype "passive"))
      (node (ref "IC2") (pin "IN_1") (pinfunction "IN_1_IN_1") (pintype "bidirectional"))
      (node (ref "IC2") (pin "IN_2") (pinfunction "IN_2_IN_2") (pintype "bidirectional"))
      (node (ref "IC2") (pin "IN_3") (pinfunction "IN_3_IN_3") (pintype "bidirectional"))
    )
    (net (code "34") (name "Net-(E4-1-Pad10)") (class "Default")
      (node (ref "E4") (pin "1") (pinfunction "1_1") (pintype "passive"))
      (node (ref "E4") (pin "10") (pinfunction "1_10") (pintype "passive"))
      (node (ref "E4") (pin "11") (pinfunction "1_11") (pintype "passive"))
      (node (ref "E4") (pin "12") (pinfunction "1_12") (pintype "passive"))
      (node (ref "E4") (pin "13") (pinfunction "1_13") (pintype "passive"))
      (node (ref "E4") (pin "14") (pinfunction "1_14") (pintype "passive"))
      (node (ref "E4") (pin "15") (pinfunction "1_15") (pintype "passive"))
      (node (ref "E4") (pin "16") (pinfunction "1_16") (pintype "passive"))
      (node (ref "E4") (pin "2") (pinfunction "1_2") (pintype "passive"))
      (node (ref "E4") (pin "3") (pinfunction "1_3") (pintype "passive"))
      (node (ref "E4") (pin "4") (pinfunction "1_4") (pintype "passive"))
      (node (ref "E4") (pin "5") (pinfunction "1_5") (pintype "passive"))
      (node (ref "E4") (pin "6") (pinfunction "1_6") (pintype "passive"))
      (node (ref "E4") (pin "7") (pinfunction "1_7") (pintype "passive"))
      (node (ref "E4") (pin "8") (pinfunction "1_8") (pintype "passive"))
      (node (ref "E4") (pin "9") (pinfunction "1_9") (pintype "passive"))
      (node (ref "IC3") (pin "IN_1") (pinfunction "IN_1_IN_1") (pintype "bidirectional"))
      (node (ref "IC3") (pin "IN_2") (pinfunction "IN_2_IN_2") (pintype "bidirectional"))
      (node (ref "IC3") (pin "IN_3") (pinfunction "IN_3_IN_3") (pintype "bidirectional"))
    )
    (net (code "35") (name "Net-(E5-1-Pad10)") (class "Default")
      (node (ref "E5") (pin "1") (pinfunction "1_1") (pintype "passive"))
      (node (ref "E5") (pin "10") (pinfunction "1_10") (pintype "passive"))
      (node (ref "E5") (pin "11") (pinfunction "1_11") (pintype "passive"))
      (node (ref "E5") (pin "12") (pinfunction "1_12") (pintype "passive"))
      (node (ref "E5") (pin "13") (pinfunction "1_13") (pintype "passive"))
      (node (ref "E5") (pin "14") (pinfunction "1_14") (pintype "passive"))
      (node (ref "E5") (pin "15") (pinfunction "1_15") (pintype "passive"))
      (node (ref "E5") (pin "16") (pinfunction "1_16") (pintype "passive"))
      (node (ref "E5") (pin "2") (pinfunction "1_2") (pintype "passive"))
      (node (ref "E5") (pin "3") (pinfunction "1_3") (pintype "passive"))
      (node (ref "E5") (pin "4") (pinfunction "1_4") (pintype "passive"))
      (node (ref "E5") (pin "5") (pinfunction "1_5") (pintype "passive"))
      (node (ref "E5") (pin "6") (pinfunction "1_6") (pintype "passive"))
      (node (ref "E5") (pin "7") (pinfunction "1_7") (pintype "passive"))
      (node (ref "E5") (pin "8") (pinfunction "1_8") (pintype "passive"))
      (node (ref "E5") (pin "9") (pinfunction "1_9") (pintype "passive"))
      (node (ref "IC4") (pin "IN_1") (pinfunction "IN_1_IN_1") (pintype "bidirectional"))
      (node (ref "IC4") (pin "IN_2") (pinfunction "IN_2_IN_2") (pintype "bidirectional"))
      (node (ref "IC4") (pin "IN_3") (pinfunction "IN_3_IN_3") (pintype "bidirectional"))
    )
    (net (code "36") (name "Net-(E6-1-Pad10)") (class "Default")
      (node (ref "E6") (pin "1") (pinfunction "1_1") (pintype "passive"))
      (node (ref "E6") (pin "10") (pinfunction "1_10") (pintype "passive"))
      (node (ref "E6") (pin "11") (pinfunction "1_11") (pintype "passive"))
      (node (ref "E6") (pin "12") (pinfunction "1_12") (pintype "passive"))
      (node (ref "E6") (pin "13") (pinfunction "1_13") (pintype "passive"))
      (node (ref "E6") (pin "14") (pinfunction "1_14") (pintype "passive"))
      (node (ref "E6") (pin "15") (pinfunction "1_15") (pintype "passive"))
      (node (ref "E6") (pin "16") (pinfunction "1_16") (pintype "passive"))
      (node (ref "E6") (pin "2") (pinfunction "1_2") (pintype "passive"))
      (node (ref "E6") (pin "3") (pinfunction "1_3") (pintype "passive"))
      (node (ref "E6") (pin "4") (pinfunction "1_4") (pintype "passive"))
      (node (ref "E6") (pin "5") (pinfunction "1_5") (pintype "passive"))
      (node (ref "E6") (pin "6") (pinfunction "1_6") (pintype "passive"))
      (node (ref "E6") (pin "7") (pinfunction "1_7") (pintype "passive"))
      (node (ref "E6") (pin "8") (pinfunction "1_8") (pintype "passive"))
      (node (ref "E6") (pin "9") (pinfunction "1_9") (pintype "passive"))
      (node (ref "IC1") (pin "OUT_1") (pinfunction "OUT_1_OUT_1") (pintype "bidirectional"))
      (node (ref "IC1") (pin "OUT_2") (pinfunction "OUT_2_OUT_2") (pintype "bidirectional"))
      (node (ref "IC1") (pin "OUT_3") (pinfunction "OUT_3_OUT_3") (pintype "bidirectional"))
    )
    (net (code "37") (name "Net-(E7-1-Pad10)") (class "Default")
      (node (ref "E7") (pin "1") (pinfunction "1_1") (pintype "passive"))
      (node (ref "E7") (pin "10") (pinfunction "1_10") (pintype "passive"))
      (node (ref "E7") (pin "11") (pinfunction "1_11") (pintype "passive"))
      (node (ref "E7") (pin "12") (pinfunction "1_12") (pintype "passive"))
      (node (ref "E7") (pin "13") (pinfunction "1_13") (pintype "passive"))
      (node (ref "E7") (pin "14") (pinfunction "1_14") (pintype "passive"))
      (node (ref "E7") (pin "15") (pinfunction "1_15") (pintype "passive"))
      (node (ref "E7") (pin "16") (pinfunction "1_16") (pintype "passive"))
      (node (ref "E7") (pin "2") (pinfunction "1_2") (pintype "passive"))
      (node (ref "E7") (pin "3") (pinfunction "1_3") (pintype "passive"))
      (node (ref "E7") (pin "4") (pinfunction "1_4") (pintype "passive"))
      (node (ref "E7") (pin "5") (pinfunction "1_5") (pintype "passive"))
      (node (ref "E7") (pin "6") (pinfunction "1_6") (pintype "passive"))
      (node (ref "E7") (pin "7") (pinfunction "1_7") (pintype "passive"))
      (node (ref "E7") (pin "8") (pinfunction "1_8") (pintype "passive"))
      (node (ref "E7") (pin "9") (pinfunction "1_9") (pintype "passive"))
      (node (ref "IC2") (pin "OUT_1") (pinfunction "OUT_1_OUT_1") (pintype "bidirectional"))
      (node (ref "IC2") (pin "OUT_2") (pinfunction "OUT_2_OUT_2") (pintype "bidirectional"))
      (node (ref "IC2") (pin "OUT_3") (pinfunction "OUT_3_OUT_3") (pintype "bidirectional"))
    )
    (net (code "38") (name "Net-(E8-1-Pad10)") (class "Default")
      (node (ref "E8") (pin "1") (pinfunction "1_1") (pintype "passive"))
      (node (ref "E8") (pin "10") (pinfunction "1_10") (pintype "passive"))
      (node (ref "E8") (pin "11") (pinfunction "1_11") (pintype "passive"))
      (node (ref "E8") (pin "12") (pinfunction "1_12") (pintype "passive"))
      (node (ref "E8") (pin "13") (pinfunction "1_13") (pintype "passive"))
      (node (ref "E8") (pin "14") (pinfunction "1_14") (pintype "passive"))
      (node (ref "E8") (pin "15") (pinfunction "1_15") (pintype "passive"))
      (node (ref "E8") (pin "16") (pinfunction "1_16") (pintype "passive"))
      (node (ref "E8") (pin "2") (pinfunction "1_2") (pintype "passive"))
      (node (ref "E8") (pin "3") (pinfunction "1_3") (pintype "passive"))
      (node (ref "E8") (pin "4") (pinfunction "1_4") (pintype "passive"))
      (node (ref "E8") (pin "5") (pinfunction "1_5") (pintype "passive"))
      (node (ref "E8") (pin "6") (pinfunction "1_6") (pintype "passive"))
      (node (ref "E8") (pin "7") (pinfunction "1_7") (pintype "passive"))
      (node (ref "E8") (pin "8") (pinfunction "1_8") (pintype "passive"))
      (node (ref "E8") (pin "9") (pinfunction "1_9") (pintype "passive"))
      (node (ref "IC3") (pin "OUT_1") (pinfunction "OUT_1_OUT_1") (pintype "bidirectional"))
      (node (ref "IC3") (pin "OUT_2") (pinfunction "OUT_2_OUT_2") (pintype "bidirectional"))
      (node (ref "IC3") (pin "OUT_3") (pinfunction "OUT_3_OUT_3") (pintype "bidirectional"))
    )
    (net (code "39") (name "Net-(E9-1-Pad10)") (class "Default")
      (node (ref "E9") (pin "1") (pinfunction "1_1") (pintype "passive"))
      (node (ref "E9") (pin "10") (pinfunction "1_10") (pintype "passive"))
      (node (ref "E9") (pin "11") (pinfunction "1_11") (pintype "passive"))
      (node (ref "E9") (pin "12") (pinfunction "1_12") (pintype "passive"))
      (node (ref "E9") (pin "13") (pinfunction "1_13") (pintype "passive"))
      (node (ref "E9") (pin "14") (pinfunction "1_14") (pintype "passive"))
      (node (ref "E9") (pin "15") (pinfunction "1_15") (pintype "passive"))
      (node (ref "E9") (pin "16") (pinfunction "1_16") (pintype "passive"))
      (node (ref "E9") (pin "2") (pinfunction "1_2") (pintype "passive"))
      (node (ref "E9") (pin "3") (pinfunction "1_3") (pintype "passive"))
      (node (ref "E9") (pin "4") (pinfunction "1_4") (pintype "passive"))
      (node (ref "E9") (pin "5") (pinfunction "1_5") (pintype "passive"))
      (node (ref "E9") (pin "6") (pinfunction "1_6") (pintype "passive"))
      (node (ref "E9") (pin "7") (pinfunction "1_7") (pintype "passive"))
      (node (ref "E9") (pin "8") (pinfunction "1_8") (pintype "passive"))
      (node (ref "E9") (pin "9") (pinfunction "1_9") (pintype "passive"))
      (node (ref "IC4") (pin "OUT_1") (pinfunction "OUT_1_OUT_1") (pintype "bidirectional"))
      (node (ref "IC4") (pin "OUT_2") (pinfunction "OUT_2_OUT_2") (pintype "bidirectional"))
      (node (ref "IC4") (pin "OUT_3") (pinfunction "OUT_3_OUT_3") (pintype "bidirectional"))
    )
    (net (code "40") (name "Net-(IC1-PadOCD)") (class "Default")
      (node (ref "IC1") (pin "OCD") (pinfunction "OCD_OCD") (pintype "bidirectional"))
      (node (ref "R1") (pin "1") (pinfunction "1_1") (pintype "passive"))
    )
    (net (code "41") (name "Net-(IC1-VREF)") (class "Default")
      (node (ref "C2") (pin "1") (pinfunction "1_1") (pintype "passive"))
      (node (ref "IC1") (pin "V-REF") (pinfunction "VREF_V-REF") (pintype "bidirectional"))
    )
    (net (code "42") (name "Net-(IC2-PadOCD)") (class "Default")
      (node (ref "IC2") (pin "OCD") (pinfunction "OCD_OCD") (pintype "bidirectional"))
      (node (ref "R2") (pin "1") (pinfunction "1_1") (pintype "passive"))
    )
    (net (code "43") (name "Net-(IC2-VREF)") (class "Default")
      (node (ref "C5") (pin "1") (pinfunction "1_1") (pintype "passive"))
      (node (ref "IC2") (pin "V-REF") (pinfunction "VREF_V-REF") (pintype "bidirectional"))
    )
    (net (code "44") (name "Net-(IC3-PadOCD)") (class "Default")
      (node (ref "IC3") (pin "OCD") (pinfunction "OCD_OCD") (pintype "bidirectional"))
      (node (ref "R3") (pin "1") (pinfunction "1_1") (pintype "passive"))
    )
    (net (code "45") (name "Net-(IC3-VREF)") (class "Default")
      (node (ref "C8") (pin "1") (pinfunction "1_1") (pintype "passive"))
      (node (ref "IC3") (pin "V-REF") (pinfunction "VREF_V-REF") (pintype "bidirectional"))
    )
    (net (code "46") (name "Net-(IC4-PadOCD)") (class "Default")
      (node (ref "IC4") (pin "OCD") (pinfunction "OCD_OCD") (pintype "bidirectional"))
      (node (ref "R4") (pin "1") (pinfunction "1_1") (pintype "passive"))
    )
    (net (code "47") (name "Net-(IC4-VREF)") (class "Default")
      (node (ref "C11") (pin "1") (pinfunction "1_1") (pintype "passive"))
      (node (ref "IC4") (pin "V-REF") (pinfunction "VREF_V-REF") (pintype "bidirectional"))
    )
    (net (code "48") (name "Net-(IC5-ADR0)") (class "Default")
      (node (ref "IC5") (pin "9") (pinfunction "ADR0_9") (pintype "passive"))
      (node (ref "SJ2") (pin "1") (pinfunction "1_1") (pintype "passive"))
    )
    (net (code "49") (name "Net-(IC5-CH1+)") (class "Default")
      (node (ref "C28") (pin "1") (pinfunction "1_1") (pintype "passive"))
      (node (ref "IC5") (pin "1") (pinfunction "CH1+_1") (pintype "input"))
      (node (ref "R17") (pin "1") (pinfunction "1_1") (pintype "passive"))
    )
    (net (code "50") (name "Net-(IC5-CH2+)") (class "Default")
      (node (ref "C27") (pin "1") (pinfunction "1_1") (pintype "passive"))
      (node (ref "IC5") (pin "3") (pinfunction "CH2+_3") (pintype "input"))
      (node (ref "R16") (pin "1") (pinfunction "1_1") (pintype "passive"))
    )
    (net (code "51") (name "Net-(IC5-CH3+)") (class "Default")
      (node (ref "C26") (pin "1") (pinfunction "1_1") (pintype "passive"))
      (node (ref "IC5") (pin "11") (pinfunction "CH3+_11") (pintype "input"))
      (node (ref "R15") (pin "1") (pinfunction "1_1") (pintype "passive"))
    )
    (net (code "52") (name "Net-(IC5-CH4+)") (class "Default")
      (node (ref "C29") (pin "1") (pinfunction "1_1") (pintype "passive"))
      (node (ref "IC5") (pin "13") (pinfunction "CH4+_13") (pintype "input"))
      (node (ref "R18") (pin "1") (pinfunction "1_1") (pintype "passive"))
    )
    (net (code "53") (name "Net-(IC5-SCL)") (class "Default")
      (node (ref "IC5") (pin "8") (pinfunction "SCL_8") (pintype "input"))
      (node (ref "IC6") (pin "28") (pinfunction "PC5(ADC5/PTCY/SCL0)_28") (pintype "bidirectional"))
      (node (ref "R6") (pin "1") (pinfunction "1_1") (pintype "passive"))
      (node (ref "X2") (pin "1") (pinfunction "S_1") (pintype "passive"))
    )
    (net (code "54") (name "Net-(IC5-SDA)") (class "Default")
      (node (ref "IC5") (pin "7") (pinfunction "SDA_7") (pintype "bidirectional"))
      (node (ref "IC6") (pin "27") (pinfunction "PC4(ADC4/PTCY/SDA0)_27") (pintype "bidirectional"))
      (node (ref "R5") (pin "1") (pinfunction "1_1") (pintype "passive"))
      (node (ref "X2") (pin "3") (pinfunction "S_3") (pintype "passive"))
    )
    (net (code "55") (name "Net-(IC6-AREF)") (class "Default")
      (node (ref "C13") (pin "1") (pinfunction "1_1") (pintype "passive"))
      (node (ref "IC6") (pin "20") (pinfunction "AREF_20") (pintype "input"))
    )
    (net (code "56") (name "Net-(IC6-PB6(XTAL1{slash}TOSC1))") (class "Default")
      (node (ref "IC6") (pin "7") (pinfunction "PB6(XTAL1/TOSC1)_7") (pintype "bidirectional"))
      (node (ref "Y1") (pin "1") (pinfunction "1_1") (pintype "passive"))
    )
    (net (code "57") (name "Net-(IC6-PB7(XTAL2{slash}TOSC2))") (class "Default")
      (node (ref "IC6") (pin "8") (pinfunction "PB7(XTAL2/TOSC2)_8") (pintype "bidirectional"))
      (node (ref "Y1") (pin "3") (pinfunction "3_3") (pintype "passive"))
    )
    (net (code "58") (name "Net-(IC6-PC0(ADC0{slash}PTCY{slash}MISO1))") (class "Default")
      (node (ref "IC6") (pin "23") (pinfunction "PC0(ADC0/PTCY/MISO1)_23") (pintype "bidirectional"))
      (node (ref "SJ3") (pin "1") (pinfunction "1_1") (pintype "passive"))
    )
    (net (code "59") (name "Net-(IC6-PC1(ADC1{slash}PTCY{slash}SCK1))") (class "Default")
      (node (ref "IC6") (pin "24") (pinfunction "PC1(ADC1/PTCY/SCK1)_24") (pintype "bidirectional"))
      (node (ref "SJ3") (pin "3") (pinfunction "3_3") (pintype "passive"))
    )
    (net (code "60") (name "Net-(IC7-A)") (class "Default")
      (node (ref "D6") (pin "1") (pinfunction "1_1") (pintype "passive"))
      (node (ref "IC7") (pin "6") (pinfunction "A_6") (pintype "bidirectional"))
      (node (ref "J1") (pin "2") (pinfunction "2_2") (pintype "passive"))
      (node (ref "J2") (pin "2") (pinfunction "2_2") (pintype "passive"))
      (node (ref "R31") (pin "2") (pinfunction "2_2") (pintype "passive"))
    )
    (net (code "61") (name "Net-(IC7-B)") (class "Default")
      (node (ref "D6") (pin "2") (pinfunction "2_2") (pintype "passive"))
      (node (ref "IC7") (pin "7") (pinfunction "B_7") (pintype "bidirectional"))
      (node (ref "J1") (pin "1") (pinfunction "1_1") (pintype "passive"))
      (node (ref "J2") (pin "1") (pinfunction "1_1") (pintype "passive"))
      (node (ref "SJ1") (pin "1") (pinfunction "1_1") (pintype "passive"))
    )
    (net (code "62") (name "Net-(IC8-FEEDBACK)") (class "Default")
      (node (ref "C37") (pin "1") (pinfunction "1_1") (pintype "passive"))
      (node (ref "IC8") (pin "7") (pinfunction "OUT_7") (pintype "output"))
      (node (ref "IC8") (pin "8") (pinfunction "FEEDBACK_8") (pintype "passive"))
      (node (ref "J8") (pin "4") (pinfunction "4_4") (pintype "passive"))
    )
    (net (code "63") (name "Net-(J8-Pad5)") (class "Default")
      (node (ref "J8") (pin "5") (pinfunction "5_5") (pintype "passive"))
      (node (ref "R21") (pin "2") (pinfunction "2_2") (pintype "passive"))
    )
    (net (code "64") (name "Net-(LED2-PadA)") (class "Default")
      (node (ref "LED2") (pin "A") (pinfunction "A_A") (pintype "passive"))
      (node (ref "R8") (pin "1") (pinfunction "1_1") (pintype "passive"))
    )
    (net (code "65") (name "Net-(LED3-PadA)") (class "Default")
      (node (ref "LED3") (pin "A") (pinfunction "A_A") (pintype "passive"))
      (node (ref "R7") (pin "1") (pinfunction "1_1") (pintype "passive"))
    )
    (net (code "66") (name "Net-(LED4-PadA)") (class "Default")
      (node (ref "LED4") (pin "A") (pinfunction "A_A") (pintype "passive"))
      (node (ref "R9") (pin "1") (pinfunction "1_1") (pintype "passive"))
    )
    (net (code "67") (name "Net-(LED6-PadC)") (class "Default")
      (node (ref "LED6") (pin "C") (pinfunction "C_C") (pintype "passive"))
      (node (ref "R14") (pin "1") (pinfunction "1_1") (pintype "passive"))
    )
    (net (code "68") (name "Net-(R31-Pad1)") (class "Default")
      (node (ref "R31") (pin "1") (pinfunction "1_1") (pintype "passive"))
      (node (ref "SJ1") (pin "2") (pinfunction "2_2") (pintype "passive"))
    )
    (net (code "69") (name "unconnected-(IC1-STBY-PadSTANDBY)") (class "Default")
      (node (ref "IC1") (pin "STANDBY") (pinfunction "STBY_STANDBY") (pintype "bidirectional"))
    )
    (net (code "70") (name "unconnected-(IC2-STBY-PadSTANDBY)") (class "Default")
      (node (ref "IC2") (pin "STANDBY") (pinfunction "STBY_STANDBY") (pintype "bidirectional"))
    )
    (net (code "71") (name "unconnected-(IC3-STBY-PadSTANDBY)") (class "Default")
      (node (ref "IC3") (pin "STANDBY") (pinfunction "STBY_STANDBY") (pintype "bidirectional"))
    )
    (net (code "72") (name "unconnected-(IC4-STBY-PadSTANDBY)") (class "Default")
      (node (ref "IC4") (pin "STANDBY") (pinfunction "STBY_STANDBY") (pintype "bidirectional"))
    )
    (net (code "73") (name "unconnected-(IC6-PC2(ADC2{slash}PTCY)-Pad25)") (class "Default")
      (node (ref "IC6") (pin "25") (pinfunction "PC2(ADC2/PTCY)_25") (pintype "bidirectional"))
    )
    (net (code "74") (name "unconnected-(IC6-PD2(PTCXY{slash}INT0{slash}OC3B{slash}OC4B)-Pad32)") (class "Default")
      (node (ref "IC6") (pin "32") (pinfunction "PD2(PTCXY/INT0/OC3B/OC4B)_32") (pintype "bidirectional"))
    )
    (net (code "75") (name "unconnected-(IC6-PD4(XCK0{slash}T0{slash}PTCXY)-Pad2)") (class "Default")
      (node (ref "IC6") (pin "2") (pinfunction "PD4(XCK0/T0/PTCXY)_2") (pintype "bidirectional"))
    )
    (net (code "76") (name "unconnected-(IC6-PE2(ADC6{slash}PTCY{slash}ICP3{slash}~{SS1})-Pad19)") (class "Default")
      (node (ref "IC6") (pin "19") (pinfunction "PE2(ADC6/PTCY/ICP3/~{SS1})_19") (pintype "bidirectional"))
    )
    (net (code "77") (name "unconnected-(IC6-PE3(ADC7{slash}PTCY{slash}T3{slash}MOSI1)-Pad22)") (class "Default")
      (node (ref "IC6") (pin "22") (pinfunction "PE3(ADC7/PTCY/T3/MOSI1)_22") (pintype "bidirectional"))
    )
    (net (code "78") (name "unconnected-(J8-Pad6)") (class "Default")
      (node (ref "J8") (pin "6") (pinfunction "6_6") (pintype "passive"))
    )
  )
)
